# Misc.net
KiCad netlist of a schematic drawn in Altium Designer
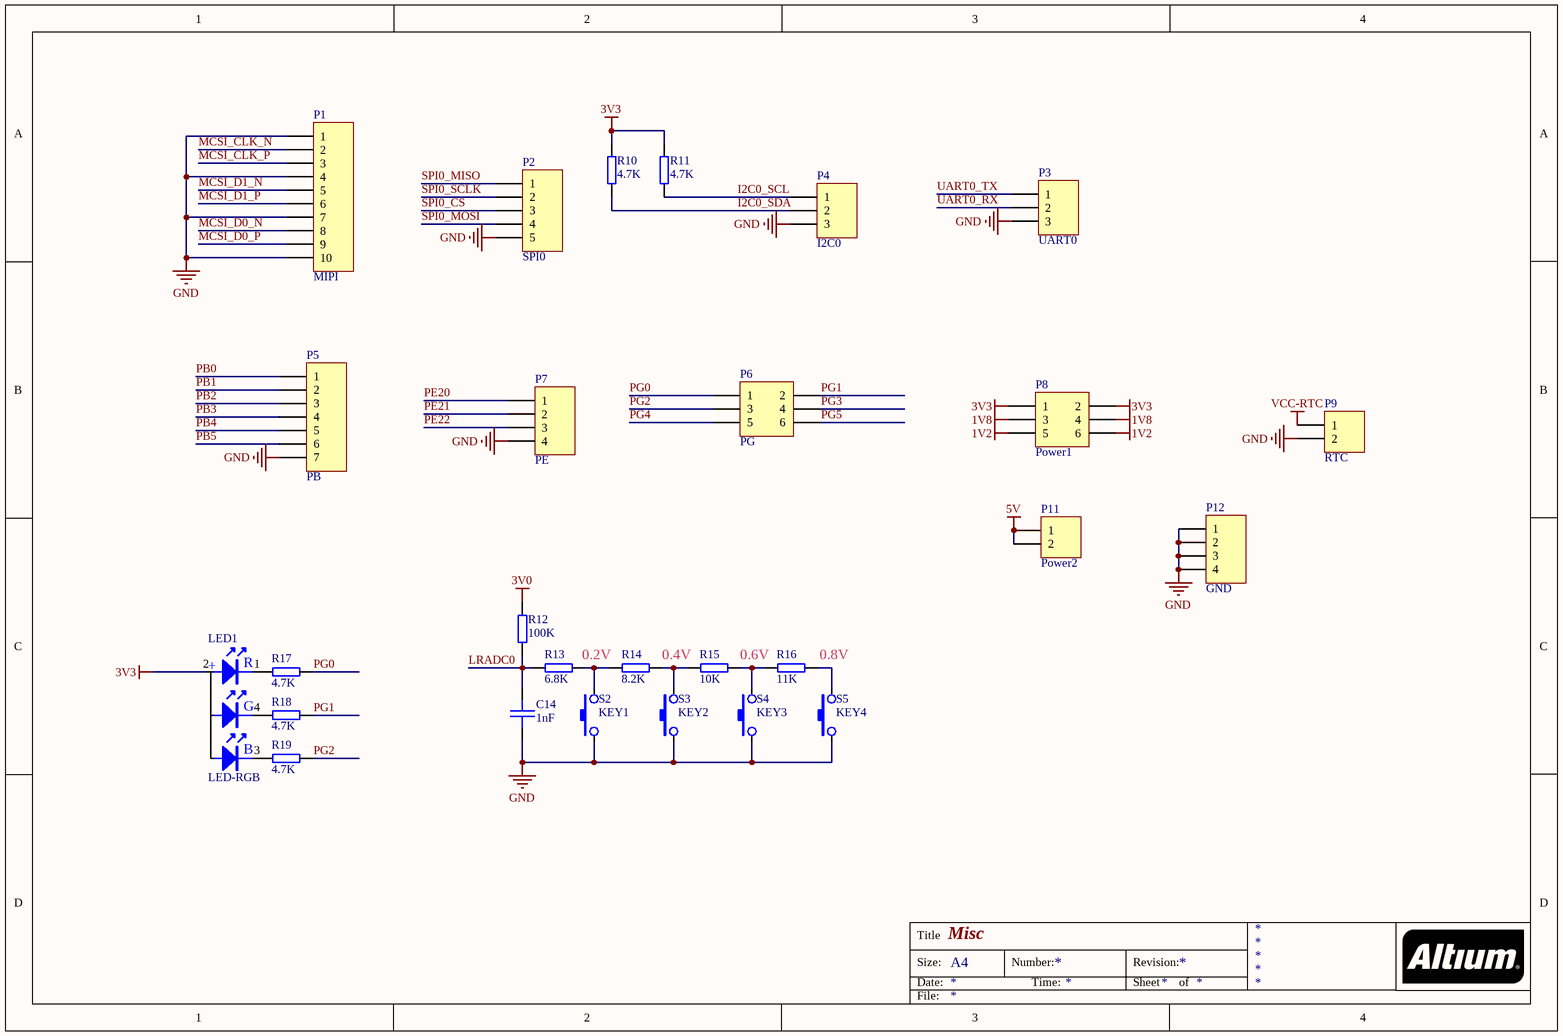
[diagram p0: Misc.SchDoc]

(export (version "E")
  (design (tool "Eeschema 10.0.6"))
  (components
    (comp (ref "C14")
      (value "1nF")
      (footprint "CAP-0603")
      (description "陶瓷贴片电容0603")
      (fields (field (name "TOLERANCE") "10%") (field (name "VOLTAGE") "50V"))
      (libsource (lib "momo") (part "C_0603"))
    )
    (comp (ref "LED1")
      (value "LED-RGB")
      (footprint "LED-RGB-3528")
      (description "RGB发光二极管")
      (libsource (lib "momo") (part "LED-RGB"))
    )
    (comp (ref "P1")
      (value "MIPI")
      (footprint "HDR1X10")
      (description "Header, 10-Pin")
      (fields (field (name "PUBLISHER") "Altium Limited"))
      (libsource (lib "Miscellaneous Connectors") (part "Header 10"))
    )
    (comp (ref "P2")
      (value "SPI0")
      (footprint "HDR1X5")
      (description "Header, 5-Pin")
      (fields (field (name "PUBLISHER") "Altium Limited"))
      (libsource (lib "Miscellaneous Connectors") (part "Header 5"))
    )
    (comp (ref "P3")
      (value "UART0")
      (footprint "HDR1X3")
      (description "Header, 3-Pin")
      (fields (field (name "PUBLISHER") "Altium Limited"))
      (libsource (lib "Miscellaneous Connectors") (part "Header 3"))
    )
    (comp (ref "P4")
      (value "I2C0")
      (footprint "HDR1X3")
      (description "Header, 3-Pin")
      (fields (field (name "PUBLISHER") "Altium Limited"))
      (libsource (lib "Miscellaneous Connectors") (part "Header 3"))
    )
    (comp (ref "P5")
      (value "PB")
      (footprint "HDR1X7")
      (description "Header, 7-Pin")
      (fields (field (name "PUBLISHER") "Altium Limited"))
      (libsource (lib "Miscellaneous Connectors") (part "Header 7"))
    )
    (comp (ref "P6")
      (value "PG")
      (footprint "HDR2X3")
      (description "Header, 3-Pin, Dual row")
      (fields (field (name "PUBLISHER") "Altium Limited"))
      (libsource (lib "Miscellaneous Connectors") (part "Header 3X2"))
    )
    (comp (ref "P7")
      (value "PE")
      (footprint "HDR1X4")
      (description "Header, 4-Pin")
      (fields (field (name "PUBLISHER") "Altium Limited"))
      (libsource (lib "Miscellaneous Connectors") (part "Header 4"))
    )
    (comp (ref "P8")
      (value "Power1")
      (footprint "HDR2X3")
      (description "Header, 3-Pin, Dual row")
      (fields (field (name "PUBLISHER") "Altium Limited"))
      (libsource (lib "Miscellaneous Connectors") (part "Header 3X2"))
    )
    (comp (ref "P9")
      (value "RTC")
      (footprint "HDR1X2")
      (description "Header, 2-Pin")
      (fields (field (name "PUBLISHER") "Altium Limited"))
      (libsource (lib "Miscellaneous Connectors") (part "Header 2"))
    )
    (comp (ref "P11")
      (value "Power2")
      (footprint "HDR1X2")
      (description "Header, 2-Pin")
      (fields (field (name "PUBLISHER") "Altium Limited"))
      (libsource (lib "Miscellaneous Connectors") (part "Header 2"))
    )
    (comp (ref "P12")
      (value "GND")
      (footprint "HDR1X4")
      (description "Header, 4-Pin")
      (fields (field (name "PUBLISHER") "Altium Limited"))
      (libsource (lib "Miscellaneous Connectors") (part "Header 4"))
    )
    (comp (ref "R10")
      (value "4.7K")
      (footprint "RES-0603")
      (description "贴片电阻0603")
      (fields (field (name "TOLERANCE") "5%") (field (name "VOLTAGE") "50V"))
      (libsource (lib "momo") (part "R_0603"))
    )
    (comp (ref "R11")
      (value "4.7K")
      (footprint "RES-0603")
      (description "贴片电阻0603")
      (fields (field (name "TOLERANCE") "5%") (field (name "VOLTAGE") "50V"))
      (libsource (lib "momo") (part "R_0603"))
    )
    (comp (ref "R12")
      (value "100K")
      (footprint "RES-0603")
      (description "贴片电阻0603")
      (fields (field (name "TOLERANCE") "5%") (field (name "VOLTAGE") "50V"))
      (libsource (lib "momo") (part "R_0603"))
    )
    (comp (ref "R13")
      (value "6.8K")
      (footprint "RES-0603")
      (description "贴片电阻0603")
      (fields (field (name "TOLERANCE") "5%") (field (name "VOLTAGE") "50V"))
      (libsource (lib "momo") (part "R_0603"))
    )
    (comp (ref "R14")
      (value "8.2K")
      (footprint "RES-0603")
      (description "贴片电阻0603")
      (fields (field (name "TOLERANCE") "5%") (field (name "VOLTAGE") "50V"))
      (libsource (lib "momo") (part "R_0603"))
    )
    (comp (ref "R15")
      (value "10K")
      (footprint "RES-0603")
      (description "贴片电阻0603")
      (fields (field (name "TOLERANCE") "5%") (field (name "VOLTAGE") "50V"))
      (libsource (lib "momo") (part "R_0603"))
    )
    (comp (ref "R16")
      (value "11K")
      (footprint "RES-0603")
      (description "贴片电阻0603")
      (fields (field (name "TOLERANCE") "5%") (field (name "VOLTAGE") "50V"))
      (libsource (lib "momo") (part "R_0603"))
    )
    (comp (ref "R17")
      (value "4.7K")
      (footprint "RES-0603")
      (description "贴片电阻0603")
      (fields (field (name "TOLERANCE") "5%") (field (name "VOLTAGE") "50V"))
      (libsource (lib "momo") (part "R_0603"))
    )
    (comp (ref "R18")
      (value "4.7K")
      (footprint "RES-0603")
      (description "贴片电阻0603")
      (fields (field (name "TOLERANCE") "5%") (field (name "VOLTAGE") "50V"))
      (libsource (lib "momo") (part "R_0603"))
    )
    (comp (ref "R19")
      (value "4.7K")
      (footprint "RES-0603")
      (description "贴片电阻0603")
      (fields (field (name "TOLERANCE") "5%") (field (name "VOLTAGE") "50V"))
      (libsource (lib "momo") (part "R_0603"))
    )
    (comp (ref "S2")
      (value "KEY1")
      (footprint "KEY_3X4X2")
      (description "轻触开关3X4X2")
      (libsource (lib "momo") (part "KEY"))
    )
    (comp (ref "S3")
      (value "KEY2")
      (footprint "KEY_3X4X2")
      (description "轻触开关3X4X2")
      (libsource (lib "momo") (part "KEY"))
    )
    (comp (ref "S4")
      (value "KEY3")
      (footprint "KEY_3X4X2")
      (description "轻触开关3X4X2")
      (libsource (lib "momo") (part "KEY"))
    )
    (comp (ref "S5")
      (value "KEY4")
      (footprint "KEY_3X4X2")
      (description "轻触开关3X4X2")
      (libsource (lib "momo") (part "KEY"))
    )
  )
  (nets
    (net (code "1") (name "/I2C0_SCL") (class "Default")
      (node (ref "P4") (pin "1") (pinfunction "1_1") (pintype "passive"))
      (node (ref "R11") (pin "1") (pinfunction "1_1") (pintype "passive"))
    )
    (net (code "2") (name "/I2C0_SDA") (class "Default")
      (node (ref "P4") (pin "2") (pinfunction "2_2") (pintype "passive"))
      (node (ref "R10") (pin "1") (pinfunction "1_1") (pintype "passive"))
    )
    (net (code "3") (name "/LRADC0") (class "Default")
      (node (ref "C14") (pin "1") (pinfunction "1_1") (pintype "passive"))
      (node (ref "R12") (pin "1") (pinfunction "1_1") (pintype "passive"))
      (node (ref "R13") (pin "2") (pinfunction "2_2") (pintype "passive"))
    )
    (net (code "4") (name "/MCSI_CLK_N") (class "Default")
      (node (ref "P1") (pin "2") (pinfunction "2_2") (pintype "passive"))
    )
    (net (code "5") (name "/MCSI_CLK_P") (class "Default")
      (node (ref "P1") (pin "3") (pinfunction "3_3") (pintype "passive"))
    )
    (net (code "6") (name "/MCSI_D0_N") (class "Default")
      (node (ref "P1") (pin "8") (pinfunction "8_8") (pintype "passive"))
    )
    (net (code "7") (name "/MCSI_D0_P") (class "Default")
      (node (ref "P1") (pin "9") (pinfunction "9_9") (pintype "passive"))
    )
    (net (code "8") (name "/MCSI_D1_N") (class "Default")
      (node (ref "P1") (pin "5") (pinfunction "5_5") (pintype "passive"))
    )
    (net (code "9") (name "/MCSI_D1_P") (class "Default")
      (node (ref "P1") (pin "6") (pinfunction "6_6") (pintype "passive"))
    )
    (net (code "10") (name "/PB0") (class "Default")
      (node (ref "P5") (pin "1") (pinfunction "1_1") (pintype "passive"))
    )
    (net (code "11") (name "/PB1") (class "Default")
      (node (ref "P5") (pin "2") (pinfunction "2_2") (pintype "passive"))
    )
    (net (code "12") (name "/PB2") (class "Default")
      (node (ref "P5") (pin "3") (pinfunction "3_3") (pintype "passive"))
    )
    (net (code "13") (name "/PB3") (class "Default")
      (node (ref "P5") (pin "4") (pinfunction "4_4") (pintype "passive"))
    )
    (net (code "14") (name "/PB4") (class "Default")
      (node (ref "P5") (pin "5") (pinfunction "5_5") (pintype "passive"))
    )
    (net (code "15") (name "/PB5") (class "Default")
      (node (ref "P5") (pin "6") (pinfunction "6_6") (pintype "passive"))
    )
    (net (code "16") (name "/PE20") (class "Default")
      (node (ref "P7") (pin "1") (pinfunction "1_1") (pintype "passive"))
    )
    (net (code "17") (name "/PE21") (class "Default")
      (node (ref "P7") (pin "2") (pinfunction "2_2") (pintype "passive"))
    )
    (net (code "18") (name "/PE22") (class "Default")
      (node (ref "P7") (pin "3") (pinfunction "3_3") (pintype "passive"))
    )
    (net (code "19") (name "/PG0") (class "Default")
      (node (ref "P6") (pin "1") (pinfunction "1_1") (pintype "passive"))
      (node (ref "R17") (pin "2") (pinfunction "2_2") (pintype "passive"))
    )
    (net (code "20") (name "/PG1") (class "Default")
      (node (ref "P6") (pin "2") (pinfunction "2_2") (pintype "passive"))
      (node (ref "R18") (pin "2") (pinfunction "2_2") (pintype "passive"))
    )
    (net (code "21") (name "/PG2") (class "Default")
      (node (ref "P6") (pin "3") (pinfunction "3_3") (pintype "passive"))
      (node (ref "R19") (pin "2") (pinfunction "2_2") (pintype "passive"))
    )
    (net (code "22") (name "/PG3") (class "Default")
      (node (ref "P6") (pin "4") (pinfunction "4_4") (pintype "passive"))
    )
    (net (code "23") (name "/PG4") (class "Default")
      (node (ref "P6") (pin "5") (pinfunction "5_5") (pintype "passive"))
    )
    (net (code "24") (name "/PG5") (class "Default")
      (node (ref "P6") (pin "6") (pinfunction "6_6") (pintype "passive"))
    )
    (net (code "25") (name "/SPI0_CS") (class "Default")
      (node (ref "P2") (pin "3") (pinfunction "3_3") (pintype "passive"))
    )
    (net (code "26") (name "/SPI0_MISO") (class "Default")
      (node (ref "P2") (pin "1") (pinfunction "1_1") (pintype "passive"))
    )
    (net (code "27") (name "/SPI0_MOSI") (class "Default")
      (node (ref "P2") (pin "4") (pinfunction "4_4") (pintype "passive"))
    )
    (net (code "28") (name "/SPI0_SCLK") (class "Default")
      (node (ref "P2") (pin "2") (pinfunction "2_2") (pintype "passive"))
    )
    (net (code "29") (name "/UART0_RX") (class "Default")
      (node (ref "P3") (pin "2") (pinfunction "2_2") (pintype "passive"))
    )
    (net (code "30") (name "/UART0_TX") (class "Default")
      (node (ref "P3") (pin "1") (pinfunction "1_1") (pintype "passive"))
    )
    (net (code "31") (name "1V2") (class "Default")
      (node (ref "P8") (pin "5") (pinfunction "5_5") (pintype "passive"))
      (node (ref "P8") (pin "6") (pinfunction "6_6") (pintype "passive"))
    )
    (net (code "32") (name "1V8") (class "Default")
      (node (ref "P8") (pin "3") (pinfunction "3_3") (pintype "passive"))
      (node (ref "P8") (pin "4") (pinfunction "4_4") (pintype "passive"))
    )
    (net (code "33") (name "3V0") (class "Default")
      (node (ref "R12") (pin "2") (pinfunction "2_2") (pintype "passive"))
    )
    (net (code "34") (name "3V3") (class "Default")
      (node (ref "LED1") (pin "2") (pinfunction "+_2") (pintype "passive"))
      (node (ref "P8") (pin "1") (pinfunction "1_1") (pintype "passive"))
      (node (ref "P8") (pin "2") (pinfunction "2_2") (pintype "passive"))
      (node (ref "R10") (pin "2") (pinfunction "2_2") (pintype "passive"))
      (node (ref "R11") (pin "2") (pinfunction "2_2") (pintype "passive"))
    )
    (net (code "35") (name "5V") (class "Default")
      (node (ref "P11") (pin "1") (pinfunction "1_1") (pintype "passive"))
      (node (ref "P11") (pin "2") (pinfunction "2_2") (pintype "passive"))
    )
    (net (code "36") (name "GND") (class "Default")
      (node (ref "C14") (pin "2") (pinfunction "2_2") (pintype "passive"))
      (node (ref "P1") (pin "1") (pinfunction "1_1") (pintype "passive"))
      (node (ref "P1") (pin "10") (pinfunction "10_10") (pintype "passive"))
      (node (ref "P1") (pin "4") (pinfunction "4_4") (pintype "passive"))
      (node (ref "P1") (pin "7") (pinfunction "7_7") (pintype "passive"))
      (node (ref "P12") (pin "1") (pinfunction "1_1") (pintype "passive"))
      (node (ref "P12") (pin "2") (pinfunction "2_2") (pintype "passive"))
      (node (ref "P12") (pin "3") (pinfunction "3_3") (pintype "passive"))
      (node (ref "P12") (pin "4") (pinfunction "4_4") (pintype "passive"))
      (node (ref "P2") (pin "5") (pinfunction "5_5") (pintype "passive"))
      (node (ref "P3") (pin "3") (pinfunction "3_3") (pintype "passive"))
      (node (ref "P4") (pin "3") (pinfunction "3_3") (pintype "passive"))
      (node (ref "P5") (pin "7") (pinfunction "7_7") (pintype "passive"))
      (node (ref "P7") (pin "4") (pinfunction "4_4") (pintype "passive"))
      (node (ref "P9") (pin "2") (pinfunction "2_2") (pintype "passive"))
      (node (ref "S2") (pin "1") (pinfunction "1_1") (pintype "passive"))
      (node (ref "S3") (pin "1") (pinfunction "1_1") (pintype "passive"))
      (node (ref "S4") (pin "1") (pinfunction "1_1") (pintype "passive"))
      (node (ref "S5") (pin "1") (pinfunction "1_1") (pintype "passive"))
    )
    (net (code "37") (name "Net-(LED1-B)") (class "Default")
      (node (ref "LED1") (pin "3") (pinfunction "B_3") (pintype "passive"))
      (node (ref "R19") (pin "1") (pinfunction "1_1") (pintype "passive"))
    )
    (net (code "38") (name "Net-(LED1-G)") (class "Default")
      (node (ref "LED1") (pin "4") (pinfunction "G_4") (pintype "passive"))
      (node (ref "R18") (pin "1") (pinfunction "1_1") (pintype "passive"))
    )
    (net (code "39") (name "Net-(LED1-R)") (class "Default")
      (node (ref "LED1") (pin "1") (pinfunction "R_1") (pintype "passive"))
      (node (ref "R17") (pin "1") (pinfunction "1_1") (pintype "passive"))
    )
    (net (code "40") (name "Net-(R13-Pad1)") (class "Default")
      (node (ref "R13") (pin "1") (pinfunction "1_1") (pintype "passive"))
      (node (ref "R14") (pin "2") (pinfunction "2_2") (pintype "passive"))
      (node (ref "S2") (pin "2") (pinfunction "2_2") (pintype "passive"))
    )
    (net (code "41") (name "Net-(R14-Pad1)") (class "Default")
      (node (ref "R14") (pin "1") (pinfunction "1_1") (pintype "passive"))
      (node (ref "R15") (pin "2") (pinfunction "2_2") (pintype "passive"))
      (node (ref "S3") (pin "2") (pinfunction "2_2") (pintype "passive"))
    )
    (net (code "42") (name "Net-(R15-Pad1)") (class "Default")
      (node (ref "R15") (pin "1") (pinfunction "1_1") (pintype "passive"))
      (node (ref "R16") (pin "2") (pinfunction "2_2") (pintype "passive"))
      (node (ref "S4") (pin "2") (pinfunction "2_2") (pintype "passive"))
    )
    (net (code "43") (name "Net-(R16-Pad1)") (class "Default")
      (node (ref "R16") (pin "1") (pinfunction "1_1") (pintype "passive"))
      (node (ref "S5") (pin "2") (pinfunction "2_2") (pintype "passive"))
    )
    (net (code "44") (name "VCC-RTC") (class "Default")
      (node (ref "P9") (pin "1") (pinfunction "1_1") (pintype "passive"))
    )
  )
)
